# OUTPUT.net
KiCad netlist of a schematic drawn in Altium Designer
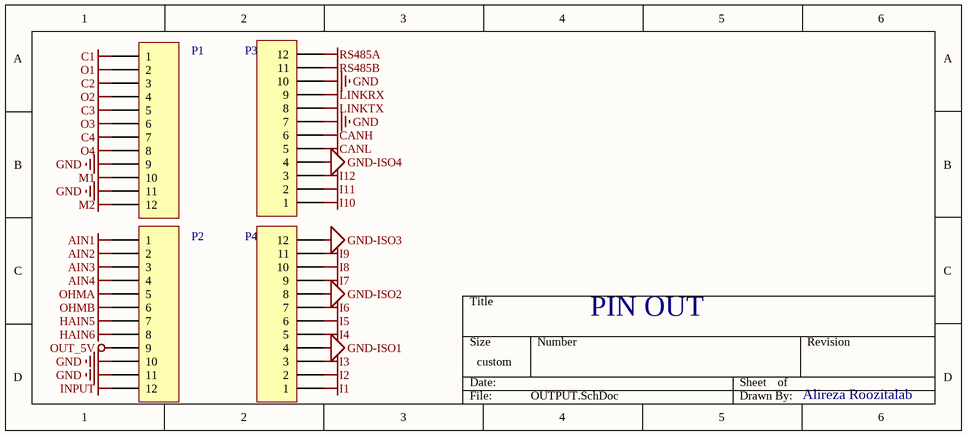
[diagram p0: OUTPUT.SchDoc]

(export (version "E")
  (design (tool "Eeschema 10.0.6"))
  (components
    (comp (ref "P1")
      (value "MHDR1X12")
      (footprint "W23112R5MILH")
      (description "Header, 12-Pin")
      (fields (field (name "PUBLISHER") "Altium Limited"))
      (libsource (lib "") (part "MHDR1X12_1"))
    )
    (comp (ref "P2")
      (value "MHDR1X12")
      (footprint "W23112R5MILH")
      (description "Header, 12-Pin")
      (fields (field (name "PUBLISHER") "Altium Limited"))
      (libsource (lib "") (part "MHDR1X12_1"))
    )
    (comp (ref "P3")
      (value "MHDR1X12")
      (footprint "W23112R5MILH")
      (description "Header, 12-Pin")
      (fields (field (name "PUBLISHER") "Altium Limited"))
      (libsource (lib "Miscellaneous Connectors") (part "MHDR1X12"))
    )
    (comp (ref "P4")
      (value "MHDR1X12")
      (footprint "W23112R5MILH")
      (description "Header, 12-Pin")
      (fields (field (name "PUBLISHER") "Altium Limited"))
      (libsource (lib "Miscellaneous Connectors") (part "MHDR1X12"))
    )
  )
  (nets
    (net (code "1") (name "AIN1") (class "Default")
      (node (ref "P2") (pin "1") (pinfunction "1_1") (pintype "passive"))
    )
    (net (code "2") (name "AIN2") (class "Default")
      (node (ref "P2") (pin "2") (pinfunction "2_2") (pintype "passive"))
    )
    (net (code "3") (name "AIN3") (class "Default")
      (node (ref "P2") (pin "3") (pinfunction "3_3") (pintype "passive"))
    )
    (net (code "4") (name "AIN4") (class "Default")
      (node (ref "P2") (pin "4") (pinfunction "4_4") (pintype "passive"))
    )
    (net (code "5") (name "C1") (class "Default")
      (node (ref "P1") (pin "1") (pinfunction "1_1") (pintype "passive"))
    )
    (net (code "6") (name "C2") (class "Default")
      (node (ref "P1") (pin "3") (pinfunction "3_3") (pintype "passive"))
    )
    (net (code "7") (name "C3") (class "Default")
      (node (ref "P1") (pin "5") (pinfunction "5_5") (pintype "passive"))
    )
    (net (code "8") (name "C4") (class "Default")
      (node (ref "P1") (pin "7") (pinfunction "7_7") (pintype "passive"))
    )
    (net (code "9") (name "CANH") (class "Default")
      (node (ref "P3") (pin "6") (pinfunction "6_6") (pintype "passive"))
    )
    (net (code "10") (name "CANL") (class "Default")
      (node (ref "P3") (pin "5") (pinfunction "5_5") (pintype "passive"))
    )
    (net (code "11") (name "GND") (class "Default")
      (node (ref "P1") (pin "11") (pinfunction "11_11") (pintype "passive"))
      (node (ref "P1") (pin "9") (pinfunction "9_9") (pintype "passive"))
      (node (ref "P2") (pin "10") (pinfunction "10_10") (pintype "passive"))
      (node (ref "P2") (pin "11") (pinfunction "11_11") (pintype "passive"))
      (node (ref "P3") (pin "10") (pinfunction "10_10") (pintype "passive"))
      (node (ref "P3") (pin "7") (pinfunction "7_7") (pintype "passive"))
    )
    (net (code "12") (name "GND-ISO1") (class "Default")
      (node (ref "P4") (pin "4") (pinfunction "4_4") (pintype "passive"))
    )
    (net (code "13") (name "GND-ISO2") (class "Default")
      (node (ref "P4") (pin "8") (pinfunction "8_8") (pintype "passive"))
    )
    (net (code "14") (name "GND-ISO3") (class "Default")
      (node (ref "P4") (pin "12") (pinfunction "12_12") (pintype "passive"))
    )
    (net (code "15") (name "GND-ISO4") (class "Default")
      (node (ref "P3") (pin "4") (pinfunction "4_4") (pintype "passive"))
    )
    (net (code "16") (name "HAIN5") (class "Default")
      (node (ref "P2") (pin "7") (pinfunction "7_7") (pintype "passive"))
    )
    (net (code "17") (name "HAIN6") (class "Default")
      (node (ref "P2") (pin "8") (pinfunction "8_8") (pintype "passive"))
    )
    (net (code "18") (name "I1") (class "Default")
      (node (ref "P4") (pin "1") (pinfunction "1_1") (pintype "passive"))
    )
    (net (code "19") (name "I2") (class "Default")
      (node (ref "P4") (pin "2") (pinfunction "2_2") (pintype "passive"))
    )
    (net (code "20") (name "I3") (class "Default")
      (node (ref "P4") (pin "3") (pinfunction "3_3") (pintype "passive"))
    )
    (net (code "21") (name "I4") (class "Default")
      (node (ref "P4") (pin "5") (pinfunction "5_5") (pintype "passive"))
    )
    (net (code "22") (name "I5") (class "Default")
      (node (ref "P4") (pin "6") (pinfunction "6_6") (pintype "passive"))
    )
    (net (code "23") (name "I6") (class "Default")
      (node (ref "P4") (pin "7") (pinfunction "7_7") (pintype "passive"))
    )
    (net (code "24") (name "I7") (class "Default")
      (node (ref "P4") (pin "9") (pinfunction "9_9") (pintype "passive"))
    )
    (net (code "25") (name "I8") (class "Default")
      (node (ref "P4") (pin "10") (pinfunction "10_10") (pintype "passive"))
    )
    (net (code "26") (name "I9") (class "Default")
      (node (ref "P4") (pin "11") (pinfunction "11_11") (pintype "passive"))
    )
    (net (code "27") (name "I10") (class "Default")
      (node (ref "P3") (pin "1") (pinfunction "1_1") (pintype "passive"))
    )
    (net (code "28") (name "I11") (class "Default")
      (node (ref "P3") (pin "2") (pinfunction "2_2") (pintype "passive"))
    )
    (net (code "29") (name "I12") (class "Default")
      (node (ref "P3") (pin "3") (pinfunction "3_3") (pintype "passive"))
    )
    (net (code "30") (name "INPUT") (class "Default")
      (node (ref "P2") (pin "12") (pinfunction "12_12") (pintype "passive"))
    )
    (net (code "31") (name "LINKRX") (class "Default")
      (node (ref "P3") (pin "9") (pinfunction "9_9") (pintype "passive"))
    )
    (net (code "32") (name "LINKTX") (class "Default")
      (node (ref "P3") (pin "8") (pinfunction "8_8") (pintype "passive"))
    )
    (net (code "33") (name "M1") (class "Default")
      (node (ref "P1") (pin "10") (pinfunction "10_10") (pintype "passive"))
    )
    (net (code "34") (name "M2") (class "Default")
      (node (ref "P1") (pin "12") (pinfunction "12_12") (pintype "passive"))
    )
    (net (code "35") (name "O1") (class "Default")
      (node (ref "P1") (pin "2") (pinfunction "2_2") (pintype "passive"))
    )
    (net (code "36") (name "O2") (class "Default")
      (node (ref "P1") (pin "4") (pinfunction "4_4") (pintype "passive"))
    )
    (net (code "37") (name "O3") (class "Default")
      (node (ref "P1") (pin "6") (pinfunction "6_6") (pintype "passive"))
    )
    (net (code "38") (name "O4") (class "Default")
      (node (ref "P1") (pin "8") (pinfunction "8_8") (pintype "passive"))
    )
    (net (code "39") (name "OHMA") (class "Default")
      (node (ref "P2") (pin "5") (pinfunction "5_5") (pintype "passive"))
    )
    (net (code "40") (name "OHMB") (class "Default")
      (node (ref "P2") (pin "6") (pinfunction "6_6") (pintype "passive"))
    )
    (net (code "41") (name "OUT_5V") (class "Default")
      (node (ref "P2") (pin "9") (pinfunction "9_9") (pintype "passive"))
    )
    (net (code "42") (name "RS485A") (class "Default")
      (node (ref "P3") (pin "12") (pinfunction "12_12") (pintype "passive"))
    )
    (net (code "43") (name "RS485B") (class "Default")
      (node (ref "P3") (pin "11") (pinfunction "11_11") (pintype "passive"))
    )
  )
)
